# 4e_-_Brake_Detection.net
KiCad netlist of a schematic drawn in Altium Designer
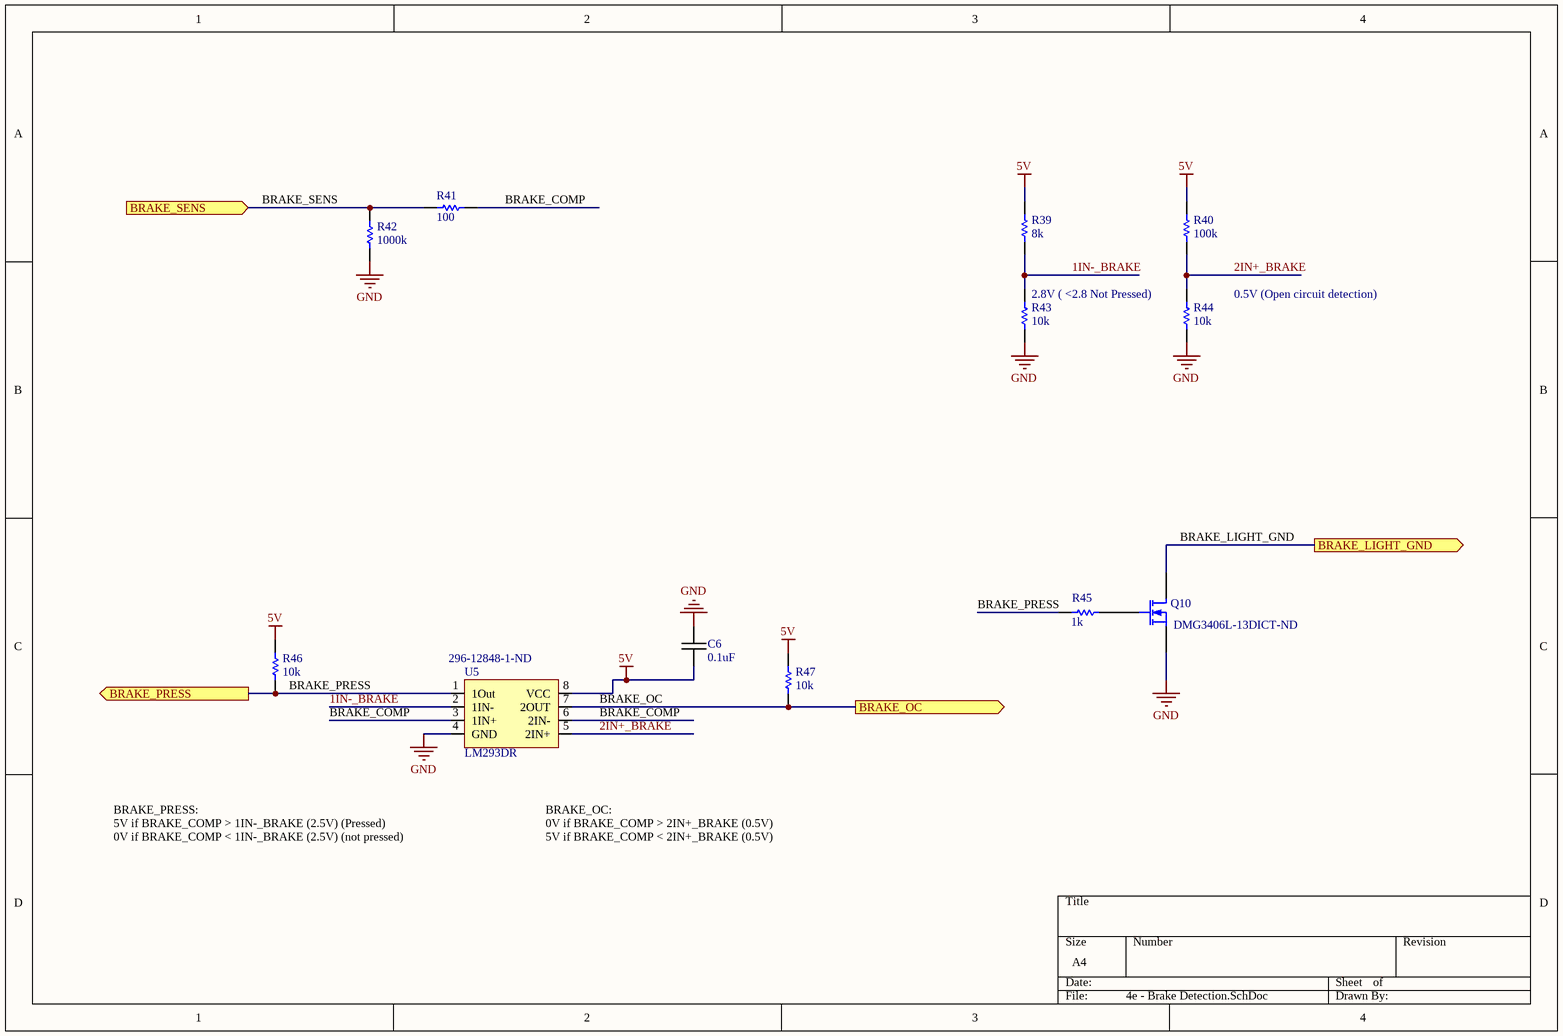
[diagram p0: 4e - Brake Detection.SchDoc]

(export (version "E")
  (design (tool "Eeschema 10.0.6"))
  (components
    (comp (ref "C6")
      (value "0.1uF")
      (footprint "1608[0603]")
      (description "CAP CER 0.1UF 50V X7R 0603")
      (fields
        (field (name "MANUFACTURER") "Kemet")
        (field (name "MANUFACTURER PART NUMBER") "C0603C104K5RACAUTO")
      )
      (libsource (lib "vh_altium_library") (part "0805C-100nF-25V-X7R-MUR"))
    )
    (comp (ref "Q10")
      (value "~")
      (footprint "SOT-23_N")
      (description "N-Channel MOSFET")
      (fields
        (field (name "MANUFACTURER") "Infineon Technologies")
        (field (name "SUPPLIER PART NUMBER 1") "DMG3406L-13DICT-ND")
        (field (name "PUBLISHER") "Altium Limited")
      )
      (libsource (lib "Miscellaneous Devices") (part "MOSFET-N"))
    )
    (comp (ref "R39")
      (value "Volt. Div. R1")
      (footprint "1608[0603]")
      (description "RES SMD 6.8K OHM 5% 1/4W 0603")
      (fields
        (field (name "MANUFACTURER") "Rohm Semiconductor")
        (field (name "MANUFACTURER PART NUMBER") "ESR03EZPJ682")
        (field (name "RESISTANCE (OHMS)") "8k")
      )
      (libsource (lib "Miscellaneous Devices") (part "Res1"))
    )
    (comp (ref "R40")
      (value "Volt. Div. R1")
      (footprint "1608[0603]")
      (description "RES SMD 6.8K OHM 5% 1/4W 0603")
      (fields
        (field (name "MANUFACTURER") "Rohm Semiconductor")
        (field (name "MANUFACTURER PART NUMBER") "ESR03EZPJ682")
        (field (name "RESISTANCE (OHMS)") "100k")
      )
      (libsource (lib "Miscellaneous Devices") (part "Res1"))
    )
    (comp (ref "R41")
      (value "100")
      (footprint "1608[0603]")
      (description "RES SMD 20K OHM 5% 1/4W 0603")
      (fields
        (field (name "MANUFACTURER") "Rohm Semiconductor")
        (field (name "MANUFACTURER PART NUMBER") "ESR03EZPJ203")
        (field (name "PUBLISHER") "Altium Limited")
      )
      (libsource (lib "Miscellaneous Devices") (part "Res1"))
    )
    (comp (ref "R42")
      (value "1000k")
      (footprint "1608[0603]")
      (description "RES SMD 20K OHM 5% 1/4W 0603")
      (fields
        (field (name "MANUFACTURER") "Rohm Semiconductor")
        (field (name "MANUFACTURER PART NUMBER") "ESR03EZPJ203")
        (field (name "PUBLISHER") "Altium Limited")
      )
      (libsource (lib "Miscellaneous Devices") (part "Res1"))
    )
    (comp (ref "R43")
      (value "10k")
      (footprint "1608[0603]")
      (description "RES SMD 20K OHM 5% 1/4W 0603")
      (fields
        (field (name "MANUFACTURER") "Rohm Semiconductor")
        (field (name "MANUFACTURER PART NUMBER") "ESR03EZPJ203")
        (field (name "PUBLISHER") "Altium Limited")
      )
      (libsource (lib "Miscellaneous Devices") (part "Res1"))
    )
    (comp (ref "R44")
      (value "10k")
      (footprint "1608[0603]")
      (description "RES SMD 20K OHM 5% 1/4W 0603")
      (fields
        (field (name "MANUFACTURER") "Rohm Semiconductor")
        (field (name "MANUFACTURER PART NUMBER") "ESR03EZPJ203")
        (field (name "PUBLISHER") "Altium Limited")
      )
      (libsource (lib "Miscellaneous Devices") (part "Res1"))
    )
    (comp (ref "R45")
      (value "1k")
      (footprint "RESC0603(1608)_L")
      (description "0603 (1608 Metric) Chip Resistor")
      (libsource (lib "Altium Content Vault") (part "RES_3"))
    )
    (comp (ref "R46")
      (value "10k")
      (footprint "1608[0603]")
      (description "RES SMD 20K OHM 5% 1/4W 0603")
      (fields
        (field (name "MANUFACTURER") "Rohm Semiconductor")
        (field (name "MANUFACTURER PART NUMBER") "ESR03EZPJ203")
        (field (name "PUBLISHER") "Altium Limited")
      )
      (libsource (lib "Miscellaneous Devices") (part "Res1"))
    )
    (comp (ref "R47")
      (value "10k")
      (footprint "1608[0603]")
      (description "RES SMD 20K OHM 5% 1/4W 0603")
      (fields
        (field (name "MANUFACTURER") "Rohm Semiconductor")
        (field (name "MANUFACTURER PART NUMBER") "ESR03EZPJ203")
        (field (name "PUBLISHER") "Altium Limited")
      )
      (libsource (lib "Miscellaneous Devices") (part "Res1"))
    )
    (comp (ref "U5")
      (value "LM293DR")
      (footprint "LM293DR")
      (description "IC Dual Comparator")
      (fields (field (name "SUPPLIER PART NUMBER 1") "296-12848-1-ND"))
      (libsource (lib "ACB_lib") (part "LM293DR"))
    )
  )
  (nets
    (net (code "1") (name "/1IN-_BRAKE") (class "Default")
      (node (ref "R39") (pin "1") (pinfunction "1_1") (pintype "passive"))
      (node (ref "R43") (pin "2") (pinfunction "2_2") (pintype "passive"))
      (node (ref "U5") (pin "2") (pinfunction "1IN-_2") (pintype "passive"))
    )
    (net (code "2") (name "/2IN+_BRAKE") (class "Default")
      (node (ref "R40") (pin "1") (pinfunction "1_1") (pintype "passive"))
      (node (ref "R44") (pin "2") (pinfunction "2_2") (pintype "passive"))
      (node (ref "U5") (pin "5") (pinfunction "2IN+_5") (pintype "passive"))
    )
    (net (code "3") (name "/BRAKE_COMP") (class "Default")
      (node (ref "R41") (pin "1") (pinfunction "1_1") (pintype "passive"))
      (node (ref "U5") (pin "3") (pinfunction "1IN+_3") (pintype "passive"))
      (node (ref "U5") (pin "6") (pinfunction "2IN-_6") (pintype "passive"))
    )
    (net (code "4") (name "/BRAKE_LIGHT_GND") (class "Default")
      (node (ref "Q10") (pin "3") (pinfunction "D_3") (pintype "passive"))
    )
    (net (code "5") (name "/BRAKE_OC") (class "Default")
      (node (ref "R47") (pin "1") (pinfunction "1_1") (pintype "passive"))
      (node (ref "U5") (pin "7") (pinfunction "2OUT_7") (pintype "passive"))
    )
    (net (code "6") (name "/BRAKE_PRESS") (class "Default")
      (node (ref "R45") (pin "1") (pinfunction "1_1") (pintype "passive"))
      (node (ref "R46") (pin "1") (pinfunction "1_1") (pintype "passive"))
      (node (ref "U5") (pin "1") (pinfunction "1Out_1") (pintype "passive"))
    )
    (net (code "7") (name "/BRAKE_SENS") (class "Default")
      (node (ref "R41") (pin "2") (pinfunction "2_2") (pintype "passive"))
      (node (ref "R42") (pin "2") (pinfunction "2_2") (pintype "passive"))
    )
    (net (code "8") (name "5V") (class "Default")
      (node (ref "C6") (pin "1") (pintype "passive"))
      (node (ref "R39") (pin "2") (pinfunction "2_2") (pintype "passive"))
      (node (ref "R40") (pin "2") (pinfunction "2_2") (pintype "passive"))
      (node (ref "R46") (pin "2") (pinfunction "2_2") (pintype "passive"))
      (node (ref "R47") (pin "2") (pinfunction "2_2") (pintype "passive"))
      (node (ref "U5") (pin "8") (pinfunction "VCC_8") (pintype "passive"))
    )
    (net (code "9") (name "GND") (class "Default")
      (node (ref "C6") (pin "2") (pintype "passive"))
      (node (ref "Q10") (pin "2") (pinfunction "S_2") (pintype "passive"))
      (node (ref "R42") (pin "1") (pinfunction "1_1") (pintype "passive"))
      (node (ref "R43") (pin "1") (pinfunction "1_1") (pintype "passive"))
      (node (ref "R44") (pin "1") (pinfunction "1_1") (pintype "passive"))
      (node (ref "U5") (pin "4") (pinfunction "GND_4") (pintype "passive"))
    )
    (net (code "10") (name "Net-(Q10-G)") (class "Default")
      (node (ref "Q10") (pin "1") (pinfunction "G_1") (pintype "passive"))
      (node (ref "R45") (pin "2") (pinfunction "2_2") (pintype "passive"))
    )
  )
)
